# BrewPi_Shield.net
KiCad netlist of a schematic drawn in EAGLE
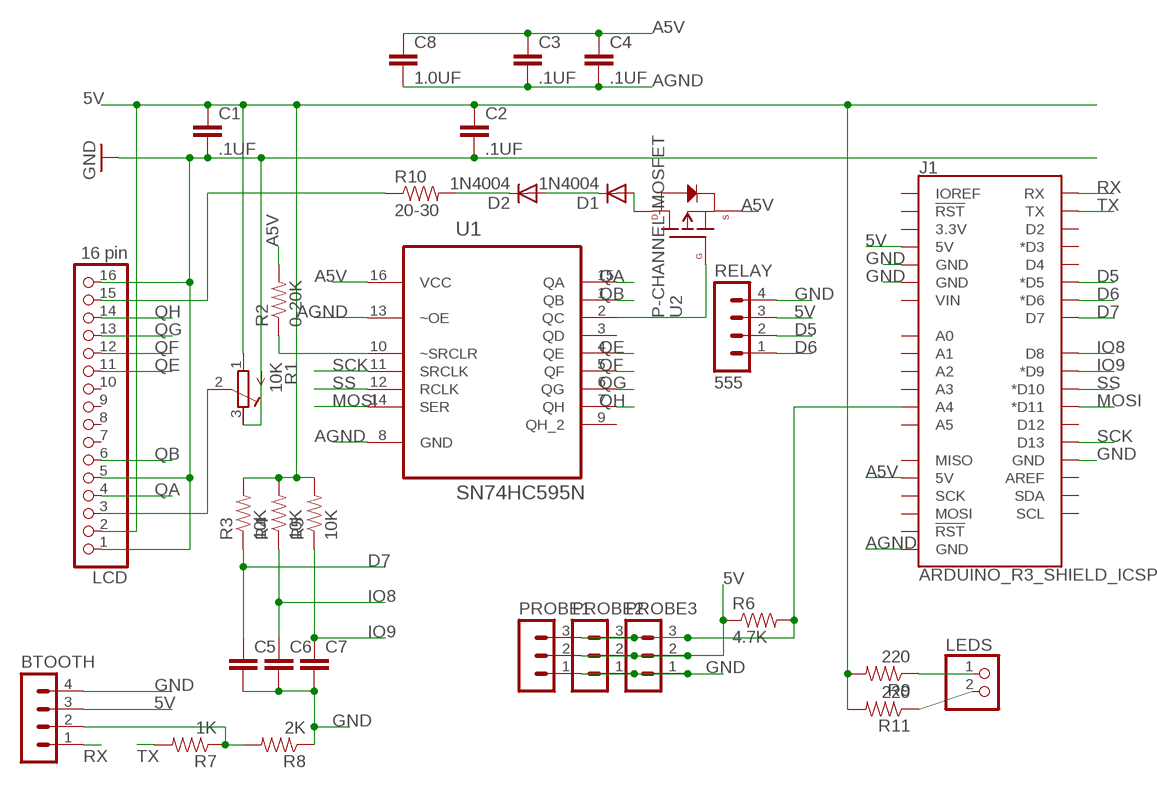
[diagram p0: schematic, sheet 1]

(export (version "E")
  (design (tool "Eeschema 10.0.6"))
  (components
    (comp (ref "BTOOTH")
      (value "MA04-1")
      (footprint "eagle-import:MA04-1")
      (libsource (lib "eagle-import") (part "MA04-1"))
    )
    (comp (ref "C1")
      (value ".1UF")
      (footprint "eagle-import:CAP-PTH-SMALL-KIT")
      (libsource (lib "eagle-import") (part "CAPKIT"))
    )
    (comp (ref "C2")
      (value ".1UF")
      (footprint "eagle-import:CAP-PTH-SMALL-KIT")
      (libsource (lib "eagle-import") (part "CAPKIT"))
    )
    (comp (ref "C3")
      (value ".1UF")
      (footprint "eagle-import:CAP-PTH-SMALL-KIT")
      (libsource (lib "eagle-import") (part "CAPKIT"))
    )
    (comp (ref "C4")
      (value ".1UF")
      (footprint "eagle-import:CAP-PTH-SMALL-KIT")
      (libsource (lib "eagle-import") (part "CAPKIT"))
    )
    (comp (ref "C5")
      (value "CAPKIT")
      (footprint "eagle-import:CAP-PTH-SMALL-KIT")
      (libsource (lib "eagle-import") (part "CAPKIT"))
    )
    (comp (ref "C6")
      (value "CAPKIT")
      (footprint "eagle-import:CAP-PTH-SMALL-KIT")
      (libsource (lib "eagle-import") (part "CAPKIT"))
    )
    (comp (ref "C7")
      (value "CAPKIT")
      (footprint "eagle-import:CAP-PTH-SMALL-KIT")
      (libsource (lib "eagle-import") (part "CAPKIT"))
    )
    (comp (ref "C8")
      (value "1.0UF")
      (footprint "eagle-import:CAP-PTH-SMALL-KIT")
      (libsource (lib "eagle-import") (part "CAPKIT"))
    )
    (comp (ref "D1")
      (value "1N4004")
      (footprint "eagle-import:DO41-10")
      (libsource (lib "eagle-import") (part "1N4004"))
    )
    (comp (ref "D2")
      (value "1N4004")
      (footprint "eagle-import:DO41-10")
      (libsource (lib "eagle-import") (part "1N4004"))
    )
    (comp (ref "J1")
      (value "ARDUINO_R3_SHIELD_ICSP")
      (footprint "eagle-import:UNO_R3_SHIELD_ICSP")
      (libsource (lib "eagle-import") (part "ARDUINO_R3_SHIELD_ICSP"))
    )
    (comp (ref "LCD")
      (value "16 pin")
      (footprint "eagle-import:1X16")
      (libsource (lib "eagle-import") (part "PINHD-1X16"))
    )
    (comp (ref "LEDS")
      (value "PINHD-1X2")
      (footprint "eagle-import:1X02")
      (libsource (lib "eagle-import") (part "PINHD-1X2"))
    )
    (comp (ref "PROBE1")
      (value "MA03-1")
      (footprint "eagle-import:MA03-1")
      (libsource (lib "eagle-import") (part "MA03-1"))
    )
    (comp (ref "PROBE2")
      (value "MA03-1")
      (footprint "eagle-import:MA03-1")
      (libsource (lib "eagle-import") (part "MA03-1"))
    )
    (comp (ref "PROBE3")
      (value "MA03-1")
      (footprint "eagle-import:MA03-1")
      (libsource (lib "eagle-import") (part "MA03-1"))
    )
    (comp (ref "R1")
      (value "10K")
      (footprint "eagle-import:RTRIM3296Y")
      (libsource (lib "eagle-import") (part "R-TRIMM3296Y"))
    )
    (comp (ref "R2")
      (value "0-20K")
      (footprint "eagle-import:AXIAL-0.3")
      (libsource (lib "eagle-import") (part "RESISTORAXIAL-0.3"))
    )
    (comp (ref "R3")
      (value "10K")
      (footprint "eagle-import:AXIAL-0.3")
      (libsource (lib "eagle-import") (part "RESISTORAXIAL-0.3"))
    )
    (comp (ref "R4")
      (value "10K")
      (footprint "eagle-import:AXIAL-0.3")
      (libsource (lib "eagle-import") (part "RESISTORAXIAL-0.3"))
    )
    (comp (ref "R5")
      (value "10K")
      (footprint "eagle-import:AXIAL-0.3")
      (libsource (lib "eagle-import") (part "RESISTORAXIAL-0.3"))
    )
    (comp (ref "R6")
      (value "4.7K")
      (footprint "eagle-import:AXIAL-0.3")
      (libsource (lib "eagle-import") (part "RESISTORAXIAL-0.3"))
    )
    (comp (ref "R7")
      (value "1K")
      (footprint "eagle-import:AXIAL-0.3")
      (libsource (lib "eagle-import") (part "RESISTORAXIAL-0.3"))
    )
    (comp (ref "R8")
      (value "2K")
      (footprint "eagle-import:AXIAL-0.3")
      (libsource (lib "eagle-import") (part "RESISTORAXIAL-0.3"))
    )
    (comp (ref "R9")
      (value "220")
      (footprint "eagle-import:AXIAL-0.3")
      (libsource (lib "eagle-import") (part "RESISTORAXIAL-0.3"))
    )
    (comp (ref "R10")
      (value "20-30")
      (footprint "eagle-import:AXIAL-0.5")
      (libsource (lib "eagle-import") (part "RESISTORPTH-1/2W"))
    )
    (comp (ref "R11")
      (value "220")
      (footprint "eagle-import:AXIAL-0.3")
      (libsource (lib "eagle-import") (part "RESISTORAXIAL-0.3"))
    )
    (comp (ref "RELAY")
      (value "555")
      (footprint "eagle-import:MA04-1")
      (libsource (lib "eagle-import") (part "MA04-1"))
    )
    (comp (ref "U1")
      (value "SN74HC595N")
      (footprint "eagle-import:DIP254P762X508-16")
      (libsource (lib "eagle-import") (part "SN74HC595N"))
    )
    (comp (ref "U2")
      (value "P-CHANNEL-MOSFET")
      (footprint "eagle-import:SOT23-3")
      (libsource (lib "eagle-import") (part "P-CHANNEL-MOSFET"))
    )
  )
  (nets
    (net (code "1") (name "/5V") (class "Default")
      (node (ref "BTOOTH") (pin "3") (pinfunction "3_3") (pintype "passive"))
      (node (ref "C1") (pin "1") (pinfunction "1_1") (pintype "passive"))
      (node (ref "C2") (pin "1") (pinfunction "1_1") (pintype "passive"))
      (node (ref "J1") (pin "5V") (pinfunction "5V_5V") (pintype "bidirectional"))
      (node (ref "LCD") (pin "2") (pinfunction "2_2") (pintype "passive"))
      (node (ref "PROBE1") (pin "2") (pinfunction "2_2") (pintype "passive"))
      (node (ref "PROBE2") (pin "2") (pinfunction "2_2") (pintype "passive"))
      (node (ref "PROBE3") (pin "2") (pinfunction "2_2") (pintype "passive"))
      (node (ref "R1") (pin "1") (pinfunction "A_1") (pintype "passive"))
      (node (ref "R11") (pin "P$2") (pinfunction "2_P$2") (pintype "passive"))
      (node (ref "R3") (pin "P$2") (pinfunction "2_P$2") (pintype "passive"))
      (node (ref "R4") (pin "P$2") (pinfunction "2_P$2") (pintype "passive"))
      (node (ref "R5") (pin "P$2") (pinfunction "2_P$2") (pintype "passive"))
      (node (ref "R6") (pin "P$1") (pinfunction "1_P$1") (pintype "passive"))
      (node (ref "R9") (pin "P$2") (pinfunction "2_P$2") (pintype "passive"))
      (node (ref "RELAY") (pin "3") (pinfunction "3_3") (pintype "passive"))
    )
    (net (code "2") (name "/A5V") (class "Default")
      (node (ref "C3") (pin "1") (pinfunction "1_1") (pintype "passive"))
      (node (ref "C4") (pin "1") (pinfunction "1_1") (pintype "passive"))
      (node (ref "C8") (pin "1") (pinfunction "1_1") (pintype "passive"))
      (node (ref "J1") (pin "5V_ICSP") (pinfunction "5V_5V_ICSP") (pintype "bidirectional"))
      (node (ref "R2") (pin "P$2") (pinfunction "2_P$2") (pintype "passive"))
      (node (ref "U1") (pin "16") (pinfunction "VCC_16") (pintype "power_in"))
      (node (ref "U2") (pin "2") (pinfunction "S_2") (pintype "passive"))
    )
    (net (code "3") (name "/AGND") (class "Default")
      (node (ref "C3") (pin "2") (pinfunction "2_2") (pintype "passive"))
      (node (ref "C4") (pin "2") (pinfunction "2_2") (pintype "passive"))
      (node (ref "C8") (pin "2") (pinfunction "2_2") (pintype "passive"))
      (node (ref "J1") (pin "GND_ICSP") (pinfunction "GND_GND_ICSP") (pintype "bidirectional"))
      (node (ref "U1") (pin "13") (pinfunction "~{OE}_13") (pintype "input"))
      (node (ref "U1") (pin "8") (pinfunction "GND_8") (pintype "passive"))
    )
    (net (code "4") (name "/D5") (class "Default")
      (node (ref "J1") (pin "D5") (pinfunction "*D5_D5") (pintype "bidirectional"))
      (node (ref "RELAY") (pin "2") (pinfunction "2_2") (pintype "passive"))
    )
    (net (code "5") (name "/D6") (class "Default")
      (node (ref "J1") (pin "D6") (pinfunction "*D6_D6") (pintype "bidirectional"))
      (node (ref "RELAY") (pin "1") (pinfunction "1_1") (pintype "passive"))
    )
    (net (code "6") (name "/D7") (class "Default")
      (node (ref "C5") (pin "1") (pinfunction "1_1") (pintype "passive"))
      (node (ref "J1") (pin "D7") (pinfunction "D7_D7") (pintype "bidirectional"))
      (node (ref "R3") (pin "P$1") (pinfunction "1_P$1") (pintype "passive"))
    )
    (net (code "7") (name "/IO8") (class "Default")
      (node (ref "C6") (pin "1") (pinfunction "1_1") (pintype "passive"))
      (node (ref "J1") (pin "D8") (pinfunction "D8_D8") (pintype "bidirectional"))
      (node (ref "R4") (pin "P$1") (pinfunction "1_P$1") (pintype "passive"))
    )
    (net (code "8") (name "/IO9") (class "Default")
      (node (ref "C7") (pin "1") (pinfunction "1_1") (pintype "passive"))
      (node (ref "J1") (pin "D9") (pinfunction "*D9_D9") (pintype "bidirectional"))
      (node (ref "R5") (pin "P$1") (pinfunction "1_P$1") (pintype "passive"))
    )
    (net (code "9") (name "/MOSI") (class "Default")
      (node (ref "J1") (pin "D11") (pinfunction "*D11_D11") (pintype "bidirectional"))
      (node (ref "U1") (pin "14") (pinfunction "SER_14") (pintype "input"))
    )
    (net (code "10") (name "/QA") (class "Default")
      (node (ref "LCD") (pin "4") (pinfunction "4_4") (pintype "passive"))
      (node (ref "U1") (pin "15") (pinfunction "QA_15") (pintype "output"))
    )
    (net (code "11") (name "/QB") (class "Default")
      (node (ref "LCD") (pin "6") (pinfunction "6_6") (pintype "passive"))
      (node (ref "U1") (pin "1") (pinfunction "QB_1") (pintype "output"))
    )
    (net (code "12") (name "/QE") (class "Default")
      (node (ref "LCD") (pin "11") (pinfunction "11_11") (pintype "passive"))
      (node (ref "U1") (pin "4") (pinfunction "QE_4") (pintype "output"))
    )
    (net (code "13") (name "/QF") (class "Default")
      (node (ref "LCD") (pin "12") (pinfunction "12_12") (pintype "passive"))
      (node (ref "U1") (pin "5") (pinfunction "QF_5") (pintype "output"))
    )
    (net (code "14") (name "/QG") (class "Default")
      (node (ref "LCD") (pin "13") (pinfunction "13_13") (pintype "passive"))
      (node (ref "U1") (pin "6") (pinfunction "QG_6") (pintype "output"))
    )
    (net (code "15") (name "/QH") (class "Default")
      (node (ref "LCD") (pin "14") (pinfunction "14_14") (pintype "passive"))
      (node (ref "U1") (pin "7") (pinfunction "QH_7") (pintype "output"))
    )
    (net (code "16") (name "/RX") (class "Default")
      (node (ref "BTOOTH") (pin "1") (pinfunction "1_1") (pintype "passive"))
      (node (ref "J1") (pin "RX") (pinfunction "RX_RX") (pintype "bidirectional"))
    )
    (net (code "17") (name "/SCK") (class "Default")
      (node (ref "J1") (pin "D13") (pinfunction "D13_D13") (pintype "bidirectional"))
      (node (ref "U1") (pin "11") (pinfunction "SRCLK_11") (pintype "input"))
    )
    (net (code "18") (name "/SS") (class "Default")
      (node (ref "J1") (pin "D10") (pinfunction "*D10_D10") (pintype "bidirectional"))
      (node (ref "U1") (pin "12") (pinfunction "RCLK_12") (pintype "input"))
    )
    (net (code "19") (name "/TX") (class "Default")
      (node (ref "J1") (pin "TX") (pinfunction "TX_TX") (pintype "bidirectional"))
      (node (ref "R7") (pin "P$2") (pinfunction "2_P$2") (pintype "passive"))
    )
    (net (code "20") (name "GND") (class "Default")
      (node (ref "BTOOTH") (pin "4") (pinfunction "4_4") (pintype "passive"))
      (node (ref "C1") (pin "2") (pinfunction "2_2") (pintype "passive"))
      (node (ref "C2") (pin "2") (pinfunction "2_2") (pintype "passive"))
      (node (ref "C5") (pin "2") (pinfunction "2_2") (pintype "passive"))
      (node (ref "C6") (pin "2") (pinfunction "2_2") (pintype "passive"))
      (node (ref "C7") (pin "2") (pinfunction "2_2") (pintype "passive"))
      (node (ref "J1") (pin "GND@0") (pinfunction "GND_GND@0") (pintype "bidirectional"))
      (node (ref "J1") (pin "GND@1") (pinfunction "GND_GND@1") (pintype "bidirectional"))
      (node (ref "J1") (pin "GND@2") (pinfunction "GND_GND@2") (pintype "bidirectional"))
      (node (ref "LCD") (pin "1") (pinfunction "1_1") (pintype "passive"))
      (node (ref "LCD") (pin "16") (pinfunction "16_16") (pintype "passive"))
      (node (ref "LCD") (pin "5") (pinfunction "5_5") (pintype "passive"))
      (node (ref "PROBE1") (pin "1") (pinfunction "1_1") (pintype "passive"))
      (node (ref "PROBE2") (pin "1") (pinfunction "1_1") (pintype "passive"))
      (node (ref "PROBE3") (pin "1") (pinfunction "1_1") (pintype "passive"))
      (node (ref "R1") (pin "3") (pinfunction "E_3") (pintype "passive"))
      (node (ref "R8") (pin "P$1") (pinfunction "1_P$1") (pintype "passive"))
      (node (ref "RELAY") (pin "4") (pinfunction "4_4") (pintype "passive"))
    )
    (net (code "21") (name "Net-(D1-PadC)") (class "Default")
      (node (ref "D1") (pin "C") (pinfunction "C_C") (pintype "passive"))
      (node (ref "D2") (pin "A") (pinfunction "A_A") (pintype "passive"))
    )
    (net (code "22") (name "Net-(R1-S)") (class "Default")
      (node (ref "LCD") (pin "3") (pinfunction "3_3") (pintype "passive"))
      (node (ref "R1") (pin "2") (pinfunction "S_2") (pintype "passive"))
    )
    (net (code "23") (name "Net-(R2-1)") (class "Default")
      (node (ref "R2") (pin "P$1") (pinfunction "1_P$1") (pintype "passive"))
      (node (ref "U1") (pin "10") (pinfunction "~{SRCLR}_10") (pintype "input"))
    )
    (net (code "24") (name "Net-(R6-2)") (class "Default")
      (node (ref "J1") (pin "A4") (pinfunction "A4_A4") (pintype "bidirectional"))
      (node (ref "PROBE1") (pin "3") (pinfunction "3_3") (pintype "passive"))
      (node (ref "PROBE2") (pin "3") (pinfunction "3_3") (pintype "passive"))
      (node (ref "PROBE3") (pin "3") (pinfunction "3_3") (pintype "passive"))
      (node (ref "R6") (pin "P$2") (pinfunction "2_P$2") (pintype "passive"))
    )
    (net (code "25") (name "Net-(R7-1)") (class "Default")
      (node (ref "BTOOTH") (pin "2") (pinfunction "2_2") (pintype "passive"))
      (node (ref "R7") (pin "P$1") (pinfunction "1_P$1") (pintype "passive"))
      (node (ref "R8") (pin "P$2") (pinfunction "2_P$2") (pintype "passive"))
    )
    (net (code "26") (name "Net-(R9-1)") (class "Default")
      (node (ref "LEDS") (pin "1") (pinfunction "1_1") (pintype "passive"))
      (node (ref "R9") (pin "P$1") (pinfunction "1_P$1") (pintype "passive"))
    )
    (net (code "27") (name "Net-(R10-1)") (class "Default")
      (node (ref "LCD") (pin "15") (pinfunction "15_15") (pintype "passive"))
      (node (ref "R10") (pin "P$1") (pinfunction "1_P$1") (pintype "passive"))
    )
    (net (code "28") (name "Net-(R10-2)") (class "Default")
      (node (ref "D2") (pin "C") (pinfunction "C_C") (pintype "passive"))
      (node (ref "R10") (pin "P$2") (pinfunction "2_P$2") (pintype "passive"))
    )
    (net (code "29") (name "Net-(R11-1)") (class "Default")
      (node (ref "LEDS") (pin "2") (pinfunction "2_2") (pintype "passive"))
      (node (ref "R11") (pin "P$1") (pinfunction "1_P$1") (pintype "passive"))
    )
    (net (code "30") (name "Net-(U1-QC)") (class "Default")
      (node (ref "U1") (pin "2") (pinfunction "QC_2") (pintype "output"))
      (node (ref "U2") (pin "1") (pinfunction "G_1") (pintype "passive"))
    )
    (net (code "31") (name "Net-(U2-D)") (class "Default")
      (node (ref "D1") (pin "A") (pinfunction "A_A") (pintype "passive"))
      (node (ref "U2") (pin "3") (pinfunction "D_3") (pintype "passive"))
    )
    (net (code "32") (name "unconnected-(J1-*D3-PadD3)") (class "Default")
      (node (ref "J1") (pin "D3") (pinfunction "*D3_D3") (pintype "bidirectional"))
    )
    (net (code "33") (name "unconnected-(J1-Pad3.3V)") (class "Default")
      (node (ref "J1") (pin "3.3V") (pinfunction "3.3V_3.3V") (pintype "bidirectional"))
    )
    (net (code "34") (name "unconnected-(J1-PadA0)") (class "Default")
      (node (ref "J1") (pin "A0") (pinfunction "A0_A0") (pintype "bidirectional"))
    )
    (net (code "35") (name "unconnected-(J1-PadA1)") (class "Default")
      (node (ref "J1") (pin "A1") (pinfunction "A1_A1") (pintype "bidirectional"))
    )
    (net (code "36") (name "unconnected-(J1-PadA2)") (class "Default")
      (node (ref "J1") (pin "A2") (pinfunction "A2_A2") (pintype "bidirectional"))
    )
    (net (code "37") (name "unconnected-(J1-PadA3)") (class "Default")
      (node (ref "J1") (pin "A3") (pinfunction "A3_A3") (pintype "bidirectional"))
    )
    (net (code "38") (name "unconnected-(J1-PadA5)") (class "Default")
      (node (ref "J1") (pin "A5") (pinfunction "A5_A5") (pintype "bidirectional"))
    )
    (net (code "39") (name "unconnected-(J1-PadAREF)") (class "Default")
      (node (ref "J1") (pin "AREF") (pinfunction "AREF_AREF") (pintype "bidirectional"))
    )
    (net (code "40") (name "unconnected-(J1-PadD2)") (class "Default")
      (node (ref "J1") (pin "D2") (pinfunction "D2_D2") (pintype "bidirectional"))
    )
    (net (code "41") (name "unconnected-(J1-PadD4)") (class "Default")
      (node (ref "J1") (pin "D4") (pinfunction "D4_D4") (pintype "bidirectional"))
    )
    (net (code "42") (name "unconnected-(J1-PadD12)") (class "Default")
      (node (ref "J1") (pin "D12") (pinfunction "D12_D12") (pintype "bidirectional"))
    )
    (net (code "43") (name "unconnected-(J1-PadIOREF)") (class "Default")
      (node (ref "J1") (pin "IOREF") (pinfunction "IOREF_IOREF") (pintype "bidirectional"))
    )
    (net (code "44") (name "unconnected-(J1-PadMISO)") (class "Default")
      (node (ref "J1") (pin "MISO") (pinfunction "MISO_MISO") (pintype "bidirectional"))
    )
    (net (code "45") (name "unconnected-(J1-PadMOSI)") (class "Default")
      (node (ref "J1") (pin "MOSI") (pinfunction "MOSI_MOSI") (pintype "bidirectional"))
    )
    (net (code "46") (name "unconnected-(J1-PadSCK)") (class "Default")
      (node (ref "J1") (pin "SCK") (pinfunction "SCK_SCK") (pintype "bidirectional"))
    )
    (net (code "47") (name "unconnected-(J1-PadSCL)") (class "Default")
      (node (ref "J1") (pin "SCL") (pinfunction "SCL_SCL") (pintype "bidirectional"))
    )
    (net (code "48") (name "unconnected-(J1-PadSDA)") (class "Default")
      (node (ref "J1") (pin "SDA") (pinfunction "SDA_SDA") (pintype "bidirectional"))
    )
    (net (code "49") (name "unconnected-(J1-PadVIN)") (class "Default")
      (node (ref "J1") (pin "VIN") (pinfunction "VIN_VIN") (pintype "bidirectional"))
    )
    (net (code "50") (name "unconnected-(J1-~{RST}-PadRES)") (class "Default")
      (node (ref "J1") (pin "RES") (pinfunction "~{RST}_RES") (pintype "bidirectional"))
    )
    (net (code "51") (name "unconnected-(J1-~{RST}-PadRST_ICSP)") (class "Default")
      (node (ref "J1") (pin "RST_ICSP") (pinfunction "~{RST}_RST_ICSP") (pintype "bidirectional"))
    )
    (net (code "52") (name "unconnected-(LCD-Pad7)") (class "Default")
      (node (ref "LCD") (pin "7") (pinfunction "7_7") (pintype "passive"))
    )
    (net (code "53") (name "unconnected-(LCD-Pad8)") (class "Default")
      (node (ref "LCD") (pin "8") (pinfunction "8_8") (pintype "passive"))
    )
    (net (code "54") (name "unconnected-(LCD-Pad9)") (class "Default")
      (node (ref "LCD") (pin "9") (pinfunction "9_9") (pintype "passive"))
    )
    (net (code "55") (name "unconnected-(LCD-Pad10)") (class "Default")
      (node (ref "LCD") (pin "10") (pinfunction "10_10") (pintype "passive"))
    )
    (net (code "56") (name "unconnected-(U1-QD-Pad3)") (class "Default")
      (node (ref "U1") (pin "3") (pinfunction "QD_3") (pintype "output"))
    )
    (net (code "57") (name "unconnected-(U1-QH_2-Pad9)") (class "Default")
      (node (ref "U1") (pin "9") (pinfunction "QH_2_9") (pintype "output"))
    )
  )
)
